# EsquematicoPotencia.net
KiCad netlist of a schematic drawn in EAGLE
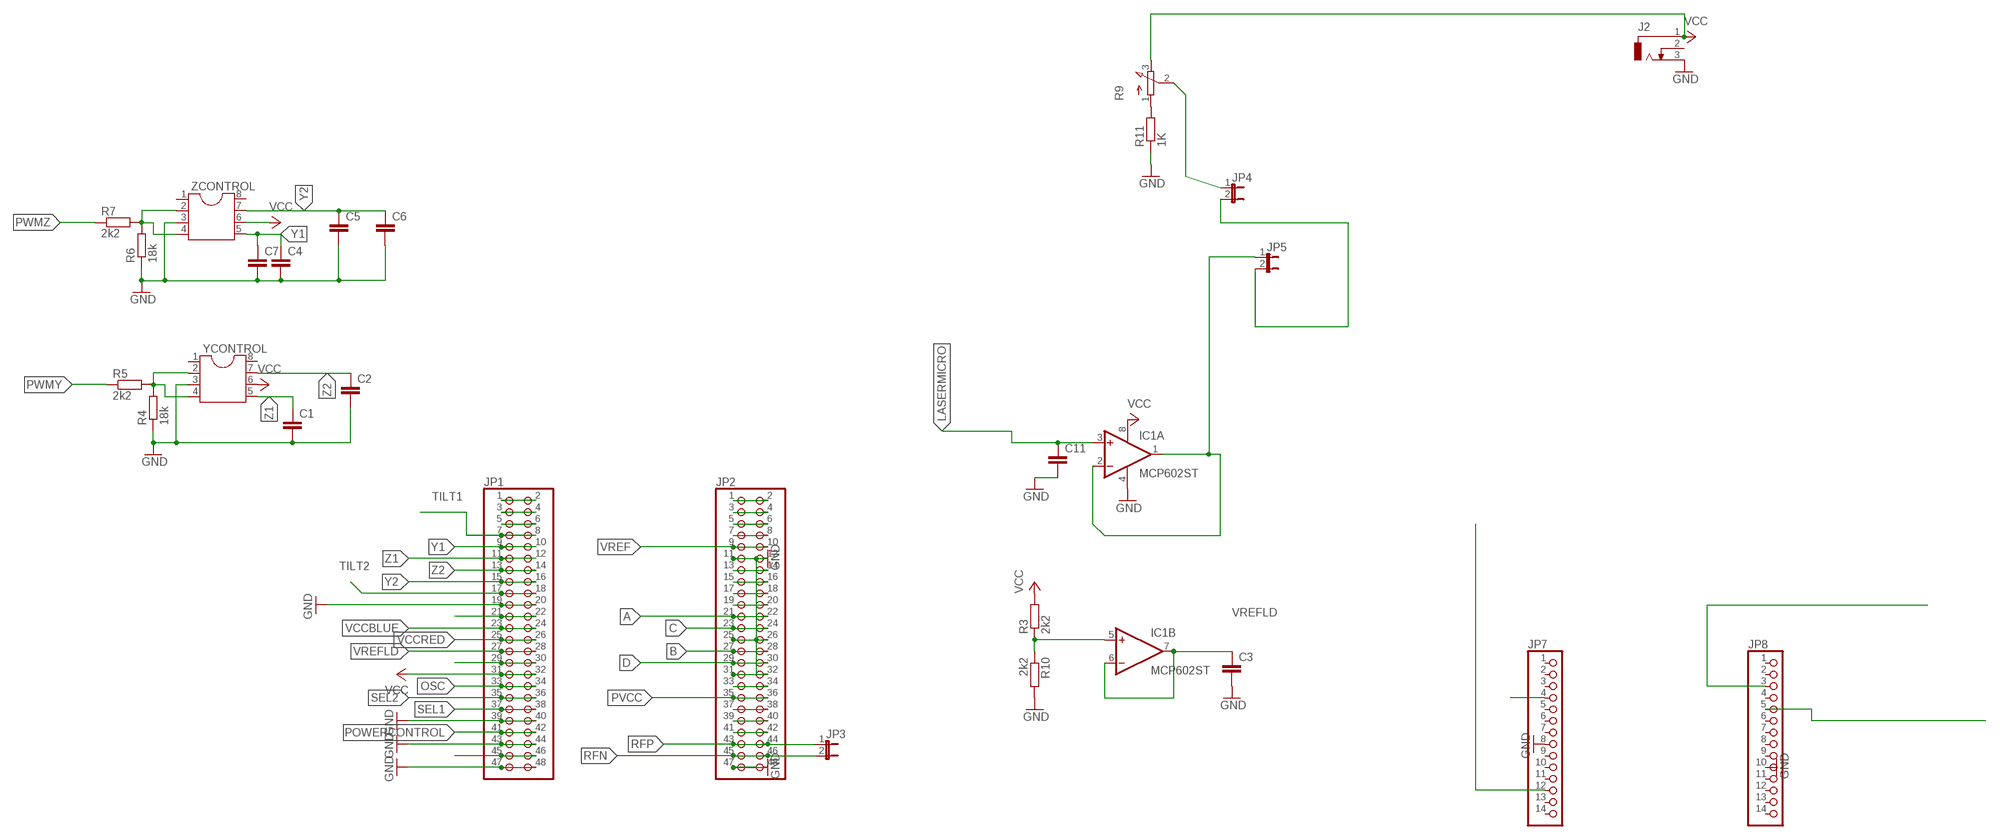
[diagram p0: schematic, sheet 1]

(export (version "E")
  (design (tool "Eeschema 10.0.6"))
  (components
    (comp (ref "C1")
      (value "C-EU025-024X044")
      (footprint "eagle-import:C025-024X044")
      (libsource (lib "eagle-import") (part "C-EU025-024X044"))
    )
    (comp (ref "C2")
      (value "C-EU025-024X044")
      (footprint "eagle-import:C025-024X044")
      (libsource (lib "eagle-import") (part "C-EU025-024X044"))
    )
    (comp (ref "C3")
      (value "C-EU025-024X044")
      (footprint "eagle-import:C025-024X044")
      (libsource (lib "eagle-import") (part "C-EU025-024X044"))
    )
    (comp (ref "C4")
      (value "C-EU025-024X044")
      (footprint "eagle-import:C025-024X044")
      (libsource (lib "eagle-import") (part "C-EU025-024X044"))
    )
    (comp (ref "C5")
      (value "C-EU025-024X044")
      (footprint "eagle-import:C025-024X044")
      (libsource (lib "eagle-import") (part "C-EU025-024X044"))
    )
    (comp (ref "C6")
      (value "C-EU025-024X044")
      (footprint "eagle-import:C025-024X044")
      (libsource (lib "eagle-import") (part "C-EU025-024X044"))
    )
    (comp (ref "C7")
      (value "C-EU025-024X044")
      (footprint "eagle-import:C025-024X044")
      (libsource (lib "eagle-import") (part "C-EU025-024X044"))
    )
    (comp (ref "C11")
      (value "C-EU025-024X044")
      (footprint "eagle-import:C025-024X044")
      (libsource (lib "eagle-import") (part "C-EU025-024X044"))
    )
    (comp (ref "IC1")
      (value "MCP602ST")
      (footprint "eagle-import:TSSOP8")
      (libsource (lib "eagle-import") (part "MCP602ST"))
    )
    (comp (ref "J2")
      (value "DCJ0303")
      (footprint "eagle-import:DCJ0303")
      (libsource (lib "eagle-import") (part "DCJ0303"))
    )
    (comp (ref "JP1")
      (value "PINHD-2X24")
      (footprint "eagle-import:2X24")
      (libsource (lib "eagle-import") (part "PINHD-2X24"))
    )
    (comp (ref "JP2")
      (value "PINHD-2X24")
      (footprint "eagle-import:2X24")
      (libsource (lib "eagle-import") (part "PINHD-2X24"))
    )
    (comp (ref "JP3")
      (value "JP1E")
      (footprint "eagle-import:JP1")
      (libsource (lib "eagle-import") (part "JP1E"))
    )
    (comp (ref "JP4")
      (value "JP1E")
      (footprint "eagle-import:JP1")
      (libsource (lib "eagle-import") (part "JP1E"))
    )
    (comp (ref "JP5")
      (value "JP1E")
      (footprint "eagle-import:JP1")
      (libsource (lib "eagle-import") (part "JP1E"))
    )
    (comp (ref "JP7")
      (value "PINHD-1X14")
      (footprint "eagle-import:1X14")
      (libsource (lib "eagle-import") (part "PINHD-1X14"))
    )
    (comp (ref "JP8")
      (value "PINHD-1X14")
      (footprint "eagle-import:1X14")
      (libsource (lib "eagle-import") (part "PINHD-1X14"))
    )
    (comp (ref "R3")
      (value "2k2")
      (footprint "eagle-import:0204_7")
      (libsource (lib "eagle-import") (part "R-EU_0204/7"))
    )
    (comp (ref "R4")
      (value "18k")
      (footprint "eagle-import:0204_7")
      (libsource (lib "eagle-import") (part "R-EU_0204/7"))
    )
    (comp (ref "R5")
      (value "2k2")
      (footprint "eagle-import:0204_7")
      (libsource (lib "eagle-import") (part "R-EU_0204/7"))
    )
    (comp (ref "R6")
      (value "18k")
      (footprint "eagle-import:0204_7")
      (libsource (lib "eagle-import") (part "R-EU_0204/7"))
    )
    (comp (ref "R7")
      (value "2k2")
      (footprint "eagle-import:0204_7")
      (libsource (lib "eagle-import") (part "R-EU_0204/7"))
    )
    (comp (ref "R9")
      (value "3RP/1610N")
      (footprint "eagle-import:3RP_1610N")
      (libsource (lib "eagle-import") (part "3RP/1610N"))
    )
    (comp (ref "R10")
      (value "2k2")
      (footprint "eagle-import:0204_7")
      (libsource (lib "eagle-import") (part "R-EU_0204/7"))
    )
    (comp (ref "R11")
      (value "1K")
      (footprint "eagle-import:0204_7")
      (libsource (lib "eagle-import") (part "R-EU_0204/7"))
    )
    (comp (ref "YCONTROL")
      (value "DIL8")
      (footprint "eagle-import:DIL08")
      (libsource (lib "eagle-import") (part "DIL8"))
    )
    (comp (ref "ZCONTROL")
      (value "DIL8")
      (footprint "eagle-import:DIL08")
      (libsource (lib "eagle-import") (part "DIL8"))
    )
  )
  (nets
    (net (code "1") (name "/TILT1") (class "Default")
      (node (ref "JP1") (pin "7") (pinfunction "7_7") (pintype "passive"))
      (node (ref "JP1") (pin "8") (pinfunction "8_8") (pintype "passive"))
    )
    (net (code "2") (name "/TILT2") (class "Default")
      (node (ref "JP1") (pin "17") (pinfunction "17_17") (pintype "passive"))
      (node (ref "JP1") (pin "18") (pinfunction "18_18") (pintype "passive"))
    )
    (net (code "3") (name "A") (class "Default")
      (node (ref "JP2") (pin "21") (pinfunction "21_21") (pintype "passive"))
      (node (ref "JP2") (pin "22") (pinfunction "22_22") (pintype "passive"))
    )
    (net (code "4") (name "B") (class "Default")
      (node (ref "JP2") (pin "27") (pinfunction "27_27") (pintype "passive"))
      (node (ref "JP2") (pin "28") (pinfunction "28_28") (pintype "passive"))
    )
    (net (code "5") (name "C") (class "Default")
      (node (ref "JP2") (pin "23") (pinfunction "23_23") (pintype "passive"))
      (node (ref "JP2") (pin "24") (pinfunction "24_24") (pintype "passive"))
    )
    (net (code "6") (name "D") (class "Default")
      (node (ref "JP2") (pin "29") (pinfunction "29_29") (pintype "passive"))
      (node (ref "JP2") (pin "30") (pinfunction "30_30") (pintype "passive"))
    )
    (net (code "7") (name "GND") (class "Default")
      (node (ref "C1") (pin "2") (pinfunction "2_2") (pintype "passive"))
      (node (ref "C11") (pin "2") (pinfunction "2_2") (pintype "passive"))
      (node (ref "C2") (pin "2") (pinfunction "2_2") (pintype "passive"))
      (node (ref "C3") (pin "2") (pinfunction "2_2") (pintype "passive"))
      (node (ref "C4") (pin "2") (pinfunction "2_2") (pintype "passive"))
      (node (ref "C5") (pin "2") (pinfunction "2_2") (pintype "passive"))
      (node (ref "C6") (pin "2") (pinfunction "2_2") (pintype "passive"))
      (node (ref "C7") (pin "2") (pinfunction "2_2") (pintype "passive"))
      (node (ref "IC1") (pin "4") (pinfunction "V-_4") (pintype "power_in"))
      (node (ref "J2") (pin "3") (pinfunction "3_3") (pintype "passive"))
      (node (ref "JP1") (pin "19") (pinfunction "19_19") (pintype "passive"))
      (node (ref "JP1") (pin "20") (pinfunction "20_20") (pintype "passive"))
      (node (ref "JP1") (pin "39") (pinfunction "39_39") (pintype "passive"))
      (node (ref "JP1") (pin "40") (pinfunction "40_40") (pintype "passive"))
      (node (ref "JP1") (pin "43") (pinfunction "43_43") (pintype "passive"))
      (node (ref "JP1") (pin "44") (pinfunction "44_44") (pintype "passive"))
      (node (ref "JP1") (pin "47") (pinfunction "47_47") (pintype "passive"))
      (node (ref "JP1") (pin "48") (pinfunction "48_48") (pintype "passive"))
      (node (ref "JP2") (pin "11") (pinfunction "11_11") (pintype "passive"))
      (node (ref "JP2") (pin "12") (pinfunction "12_12") (pintype "passive"))
      (node (ref "JP2") (pin "25") (pinfunction "25_25") (pintype "passive"))
      (node (ref "JP2") (pin "26") (pinfunction "26_26") (pintype "passive"))
      (node (ref "JP2") (pin "31") (pinfunction "31_31") (pintype "passive"))
      (node (ref "JP2") (pin "32") (pinfunction "32_32") (pintype "passive"))
      (node (ref "JP2") (pin "47") (pinfunction "47_47") (pintype "passive"))
      (node (ref "JP2") (pin "48") (pinfunction "48_48") (pintype "passive"))
      (node (ref "JP7") (pin "8") (pinfunction "8_8") (pintype "passive"))
      (node (ref "JP8") (pin "10") (pinfunction "10_10") (pintype "passive"))
      (node (ref "R10") (pin "2") (pinfunction "2_2") (pintype "passive"))
      (node (ref "R11") (pin "1") (pinfunction "1_1") (pintype "passive"))
      (node (ref "R4") (pin "1") (pinfunction "1_1") (pintype "passive"))
      (node (ref "R6") (pin "1") (pinfunction "1_1") (pintype "passive"))
      (node (ref "YCONTROL") (pin "3") (pinfunction "3_3") (pintype "passive"))
      (node (ref "ZCONTROL") (pin "3") (pinfunction "3_3") (pintype "passive"))
    )
    (net (code "8") (name "LASERMICRO") (class "Default")
      (node (ref "C11") (pin "1") (pinfunction "1_1") (pintype "passive"))
      (node (ref "IC1") (pin "3") (pinfunction "+IN_3") (pintype "input"))
      (node (ref "JP7") (pin "4") (pinfunction "4_4") (pintype "passive"))
    )
    (net (code "9") (name "Net-(IC1A--IN)") (class "Default")
      (node (ref "IC1") (pin "1") (pinfunction "OUT_1") (pintype "output"))
      (node (ref "IC1") (pin "2") (pinfunction "-IN_2") (pintype "input"))
      (node (ref "JP5") (pin "1") (pinfunction "1_1") (pintype "passive"))
    )
    (net (code "10") (name "Net-(IC1B-+IN)") (class "Default")
      (node (ref "IC1") (pin "5") (pinfunction "+IN_5") (pintype "input"))
      (node (ref "R10") (pin "1") (pinfunction "1_1") (pintype "passive"))
      (node (ref "R3") (pin "1") (pinfunction "1_1") (pintype "passive"))
    )
    (net (code "11") (name "Net-(JP1-Pad1)") (class "Default")
      (node (ref "JP1") (pin "1") (pinfunction "1_1") (pintype "passive"))
      (node (ref "JP1") (pin "2") (pinfunction "2_2") (pintype "passive"))
    )
    (net (code "12") (name "Net-(JP1-Pad3)") (class "Default")
      (node (ref "JP1") (pin "3") (pinfunction "3_3") (pintype "passive"))
      (node (ref "JP1") (pin "4") (pinfunction "4_4") (pintype "passive"))
    )
    (net (code "13") (name "Net-(JP1-Pad5)") (class "Default")
      (node (ref "JP1") (pin "5") (pinfunction "5_5") (pintype "passive"))
      (node (ref "JP1") (pin "6") (pinfunction "6_6") (pintype "passive"))
    )
    (net (code "14") (name "Net-(JP1-Pad21)") (class "Default")
      (node (ref "JP1") (pin "21") (pinfunction "21_21") (pintype "passive"))
      (node (ref "JP1") (pin "22") (pinfunction "22_22") (pintype "passive"))
    )
    (net (code "15") (name "Net-(JP1-Pad29)") (class "Default")
      (node (ref "JP1") (pin "29") (pinfunction "29_29") (pintype "passive"))
      (node (ref "JP1") (pin "30") (pinfunction "30_30") (pintype "passive"))
    )
    (net (code "16") (name "Net-(JP1-Pad45)") (class "Default")
      (node (ref "JP1") (pin "45") (pinfunction "45_45") (pintype "passive"))
      (node (ref "JP1") (pin "46") (pinfunction "46_46") (pintype "passive"))
    )
    (net (code "17") (name "Net-(JP2-Pad1)") (class "Default")
      (node (ref "JP2") (pin "1") (pinfunction "1_1") (pintype "passive"))
      (node (ref "JP2") (pin "2") (pinfunction "2_2") (pintype "passive"))
    )
    (net (code "18") (name "Net-(JP2-Pad3)") (class "Default")
      (node (ref "JP2") (pin "3") (pinfunction "3_3") (pintype "passive"))
      (node (ref "JP2") (pin "4") (pinfunction "4_4") (pintype "passive"))
    )
    (net (code "19") (name "Net-(JP2-Pad5)") (class "Default")
      (node (ref "JP2") (pin "5") (pinfunction "5_5") (pintype "passive"))
      (node (ref "JP2") (pin "6") (pinfunction "6_6") (pintype "passive"))
    )
    (net (code "20") (name "Net-(JP2-Pad7)") (class "Default")
      (node (ref "JP2") (pin "7") (pinfunction "7_7") (pintype "passive"))
      (node (ref "JP2") (pin "8") (pinfunction "8_8") (pintype "passive"))
    )
    (net (code "21") (name "Net-(JP2-Pad13)") (class "Default")
      (node (ref "JP2") (pin "13") (pinfunction "13_13") (pintype "passive"))
      (node (ref "JP2") (pin "14") (pinfunction "14_14") (pintype "passive"))
    )
    (net (code "22") (name "Net-(JP2-Pad15)") (class "Default")
      (node (ref "JP2") (pin "15") (pinfunction "15_15") (pintype "passive"))
      (node (ref "JP2") (pin "16") (pinfunction "16_16") (pintype "passive"))
    )
    (net (code "23") (name "Net-(JP2-Pad17)") (class "Default")
      (node (ref "JP2") (pin "17") (pinfunction "17_17") (pintype "passive"))
      (node (ref "JP2") (pin "18") (pinfunction "18_18") (pintype "passive"))
    )
    (net (code "24") (name "Net-(JP2-Pad19)") (class "Default")
      (node (ref "JP2") (pin "19") (pinfunction "19_19") (pintype "passive"))
      (node (ref "JP2") (pin "20") (pinfunction "20_20") (pintype "passive"))
    )
    (net (code "25") (name "Net-(JP2-Pad33)") (class "Default")
      (node (ref "JP2") (pin "33") (pinfunction "33_33") (pintype "passive"))
      (node (ref "JP2") (pin "34") (pinfunction "34_34") (pintype "passive"))
    )
    (net (code "26") (name "Net-(JP2-Pad37)") (class "Default")
      (node (ref "JP2") (pin "37") (pinfunction "37_37") (pintype "passive"))
      (node (ref "JP2") (pin "38") (pinfunction "38_38") (pintype "passive"))
    )
    (net (code "27") (name "Net-(JP2-Pad39)") (class "Default")
      (node (ref "JP2") (pin "39") (pinfunction "39_39") (pintype "passive"))
      (node (ref "JP2") (pin "40") (pinfunction "40_40") (pintype "passive"))
    )
    (net (code "28") (name "Net-(JP2-Pad41)") (class "Default")
      (node (ref "JP2") (pin "41") (pinfunction "41_41") (pintype "passive"))
      (node (ref "JP2") (pin "42") (pinfunction "42_42") (pintype "passive"))
    )
    (net (code "29") (name "Net-(R4-Pad2)") (class "Default")
      (node (ref "R4") (pin "2") (pinfunction "2_2") (pintype "passive"))
      (node (ref "R5") (pin "2") (pinfunction "2_2") (pintype "passive"))
      (node (ref "YCONTROL") (pin "2") (pinfunction "2_2") (pintype "passive"))
      (node (ref "YCONTROL") (pin "4") (pinfunction "4_4") (pintype "passive"))
    )
    (net (code "30") (name "Net-(R6-Pad2)") (class "Default")
      (node (ref "R6") (pin "2") (pinfunction "2_2") (pintype "passive"))
      (node (ref "R7") (pin "2") (pinfunction "2_2") (pintype "passive"))
      (node (ref "ZCONTROL") (pin "2") (pinfunction "2_2") (pintype "passive"))
      (node (ref "ZCONTROL") (pin "4") (pinfunction "4_4") (pintype "passive"))
    )
    (net (code "31") (name "Net-(R9-A)") (class "Default")
      (node (ref "R11") (pin "2") (pinfunction "2_2") (pintype "passive"))
      (node (ref "R9") (pin "1") (pinfunction "A_1") (pintype "passive"))
    )
    (net (code "32") (name "Net-(R9-S)") (class "Default")
      (node (ref "JP4") (pin "1") (pinfunction "1_1") (pintype "passive"))
      (node (ref "R9") (pin "2") (pinfunction "S_2") (pintype "passive"))
    )
    (net (code "33") (name "OSC") (class "Default")
      (node (ref "JP1") (pin "33") (pinfunction "33_33") (pintype "passive"))
      (node (ref "JP1") (pin "34") (pinfunction "34_34") (pintype "passive"))
    )
    (net (code "34") (name "POWERCONTROL") (class "Default")
      (node (ref "JP1") (pin "41") (pinfunction "41_41") (pintype "passive"))
      (node (ref "JP1") (pin "42") (pinfunction "42_42") (pintype "passive"))
      (node (ref "JP4") (pin "2") (pinfunction "2_2") (pintype "passive"))
      (node (ref "JP5") (pin "2") (pinfunction "2_2") (pintype "passive"))
    )
    (net (code "35") (name "PVCC") (class "Default")
      (node (ref "JP2") (pin "35") (pinfunction "35_35") (pintype "passive"))
      (node (ref "JP2") (pin "36") (pinfunction "36_36") (pintype "passive"))
    )
    (net (code "36") (name "PWMY") (class "Default")
      (node (ref "JP7") (pin "12") (pinfunction "12_12") (pintype "passive"))
      (node (ref "R5") (pin "1") (pinfunction "1_1") (pintype "passive"))
    )
    (net (code "37") (name "PWMZ") (class "Default")
      (node (ref "JP8") (pin "3") (pinfunction "3_3") (pintype "passive"))
      (node (ref "R7") (pin "1") (pinfunction "1_1") (pintype "passive"))
    )
    (net (code "38") (name "RFN") (class "Default")
      (node (ref "JP2") (pin "45") (pinfunction "45_45") (pintype "passive"))
      (node (ref "JP2") (pin "46") (pinfunction "46_46") (pintype "passive"))
      (node (ref "JP3") (pin "2") (pinfunction "2_2") (pintype "passive"))
    )
    (net (code "39") (name "RFP") (class "Default")
      (node (ref "JP2") (pin "43") (pinfunction "43_43") (pintype "passive"))
      (node (ref "JP2") (pin "44") (pinfunction "44_44") (pintype "passive"))
      (node (ref "JP3") (pin "1") (pinfunction "1_1") (pintype "passive"))
    )
    (net (code "40") (name "SEL1") (class "Default")
      (node (ref "JP1") (pin "37") (pinfunction "37_37") (pintype "passive"))
      (node (ref "JP1") (pin "38") (pinfunction "38_38") (pintype "passive"))
    )
    (net (code "41") (name "SEL2") (class "Default")
      (node (ref "JP1") (pin "35") (pinfunction "35_35") (pintype "passive"))
      (node (ref "JP1") (pin "36") (pinfunction "36_36") (pintype "passive"))
    )
    (net (code "42") (name "VCC") (class "Default")
      (node (ref "IC1") (pin "8") (pinfunction "V+_8") (pintype "power_in"))
      (node (ref "J2") (pin "1") (pinfunction "1_1") (pintype "passive"))
      (node (ref "JP1") (pin "31") (pinfunction "31_31") (pintype "passive"))
      (node (ref "JP1") (pin "32") (pinfunction "32_32") (pintype "passive"))
      (node (ref "R3") (pin "2") (pinfunction "2_2") (pintype "passive"))
      (node (ref "R9") (pin "3") (pinfunction "E_3") (pintype "passive"))
      (node (ref "YCONTROL") (pin "6") (pinfunction "6_6") (pintype "passive"))
      (node (ref "ZCONTROL") (pin "6") (pinfunction "6_6") (pintype "passive"))
    )
    (net (code "43") (name "VCCBLUE") (class "Default")
      (node (ref "JP1") (pin "23") (pinfunction "23_23") (pintype "passive"))
      (node (ref "JP1") (pin "24") (pinfunction "24_24") (pintype "passive"))
    )
    (net (code "44") (name "VCCRED") (class "Default")
      (node (ref "JP1") (pin "25") (pinfunction "25_25") (pintype "passive"))
      (node (ref "JP1") (pin "26") (pinfunction "26_26") (pintype "passive"))
    )
    (net (code "45") (name "VREF") (class "Default")
      (node (ref "JP2") (pin "10") (pinfunction "10_10") (pintype "passive"))
      (node (ref "JP2") (pin "9") (pinfunction "9_9") (pintype "passive"))
    )
    (net (code "46") (name "VREFLD") (class "Default")
      (node (ref "C3") (pin "1") (pinfunction "1_1") (pintype "passive"))
      (node (ref "IC1") (pin "6") (pinfunction "-IN_6") (pintype "input"))
      (node (ref "IC1") (pin "7") (pinfunction "OUT_7") (pintype "output"))
      (node (ref "JP1") (pin "27") (pinfunction "27_27") (pintype "passive"))
      (node (ref "JP1") (pin "28") (pinfunction "28_28") (pintype "passive"))
    )
    (net (code "47") (name "Y1") (class "Default")
      (node (ref "C4") (pin "1") (pinfunction "1_1") (pintype "passive"))
      (node (ref "C7") (pin "1") (pinfunction "1_1") (pintype "passive"))
      (node (ref "JP1") (pin "10") (pinfunction "10_10") (pintype "passive"))
      (node (ref "JP1") (pin "9") (pinfunction "9_9") (pintype "passive"))
      (node (ref "ZCONTROL") (pin "5") (pinfunction "5_5") (pintype "passive"))
    )
    (net (code "48") (name "Y2") (class "Default")
      (node (ref "C5") (pin "1") (pinfunction "1_1") (pintype "passive"))
      (node (ref "C6") (pin "1") (pinfunction "1_1") (pintype "passive"))
      (node (ref "JP1") (pin "15") (pinfunction "15_15") (pintype "passive"))
      (node (ref "JP1") (pin "16") (pinfunction "16_16") (pintype "passive"))
      (node (ref "ZCONTROL") (pin "7") (pinfunction "7_7") (pintype "passive"))
    )
    (net (code "49") (name "Z1") (class "Default")
      (node (ref "C1") (pin "1") (pinfunction "1_1") (pintype "passive"))
      (node (ref "JP1") (pin "11") (pinfunction "11_11") (pintype "passive"))
      (node (ref "JP1") (pin "12") (pinfunction "12_12") (pintype "passive"))
      (node (ref "YCONTROL") (pin "5") (pinfunction "5_5") (pintype "passive"))
    )
    (net (code "50") (name "Z2") (class "Default")
      (node (ref "C2") (pin "1") (pinfunction "1_1") (pintype "passive"))
      (node (ref "JP1") (pin "13") (pinfunction "13_13") (pintype "passive"))
      (node (ref "JP1") (pin "14") (pinfunction "14_14") (pintype "passive"))
      (node (ref "YCONTROL") (pin "7") (pinfunction "7_7") (pintype "passive"))
    )
    (net (code "51") (name "unconnected-(J2-Pad2)") (class "Default")
      (node (ref "J2") (pin "2") (pinfunction "2_2") (pintype "passive"))
    )
    (net (code "52") (name "unconnected-(JP7-Pad1)") (class "Default")
      (node (ref "JP7") (pin "1") (pinfunction "1_1") (pintype "passive"))
    )
    (net (code "53") (name "unconnected-(JP7-Pad2)") (class "Default")
      (node (ref "JP7") (pin "2") (pinfunction "2_2") (pintype "passive"))
    )
    (net (code "54") (name "unconnected-(JP7-Pad3)") (class "Default")
      (node (ref "JP7") (pin "3") (pinfunction "3_3") (pintype "passive"))
    )
    (net (code "55") (name "unconnected-(JP7-Pad5)") (class "Default")
      (node (ref "JP7") (pin "5") (pinfunction "5_5") (pintype "passive"))
    )
    (net (code "56") (name "unconnected-(JP7-Pad6)") (class "Default")
      (node (ref "JP7") (pin "6") (pinfunction "6_6") (pintype "passive"))
    )
    (net (code "57") (name "unconnected-(JP7-Pad7)") (class "Default")
      (node (ref "JP7") (pin "7") (pinfunction "7_7") (pintype "passive"))
    )
    (net (code "58") (name "unconnected-(JP7-Pad9)") (class "Default")
      (node (ref "JP7") (pin "9") (pinfunction "9_9") (pintype "passive"))
    )
    (net (code "59") (name "unconnected-(JP7-Pad10)") (class "Default")
      (node (ref "JP7") (pin "10") (pinfunction "10_10") (pintype "passive"))
    )
    (net (code "60") (name "unconnected-(JP7-Pad11)") (class "Default")
      (node (ref "JP7") (pin "11") (pinfunction "11_11") (pintype "passive"))
    )
    (net (code "61") (name "unconnected-(JP7-Pad13)") (class "Default")
      (node (ref "JP7") (pin "13") (pinfunction "13_13") (pintype "passive"))
    )
    (net (code "62") (name "unconnected-(JP7-Pad14)") (class "Default")
      (node (ref "JP7") (pin "14") (pinfunction "14_14") (pintype "passive"))
    )
    (net (code "63") (name "unconnected-(JP8-Pad1)") (class "Default")
      (node (ref "JP8") (pin "1") (pinfunction "1_1") (pintype "passive"))
    )
    (net (code "64") (name "unconnected-(JP8-Pad2)") (class "Default")
      (node (ref "JP8") (pin "2") (pinfunction "2_2") (pintype "passive"))
    )
    (net (code "65") (name "unconnected-(JP8-Pad4)") (class "Default")
      (node (ref "JP8") (pin "4") (pinfunction "4_4") (pintype "passive"))
    )
    (net (code "66") (name "unconnected-(JP8-Pad5)") (class "Default")
      (node (ref "JP8") (pin "5") (pinfunction "5_5") (pintype "passive"))
    )
    (net (code "67") (name "unconnected-(JP8-Pad6)") (class "Default")
      (node (ref "JP8") (pin "6") (pinfunction "6_6") (pintype "passive"))
    )
    (net (code "68") (name "unconnected-(JP8-Pad7)") (class "Default")
      (node (ref "JP8") (pin "7") (pinfunction "7_7") (pintype "passive"))
    )
    (net (code "69") (name "unconnected-(JP8-Pad8)") (class "Default")
      (node (ref "JP8") (pin "8") (pinfunction "8_8") (pintype "passive"))
    )
    (net (code "70") (name "unconnected-(JP8-Pad9)") (class "Default")
      (node (ref "JP8") (pin "9") (pinfunction "9_9") (pintype "passive"))
    )
    (net (code "71") (name "unconnected-(JP8-Pad11)") (class "Default")
      (node (ref "JP8") (pin "11") (pinfunction "11_11") (pintype "passive"))
    )
    (net (code "72") (name "unconnected-(JP8-Pad12)") (class "Default")
      (node (ref "JP8") (pin "12") (pinfunction "12_12") (pintype "passive"))
    )
    (net (code "73") (name "unconnected-(JP8-Pad13)") (class "Default")
      (node (ref "JP8") (pin "13") (pinfunction "13_13") (pintype "passive"))
    )
    (net (code "74") (name "unconnected-(JP8-Pad14)") (class "Default")
      (node (ref "JP8") (pin "14") (pinfunction "14_14") (pintype "passive"))
    )
    (net (code "75") (name "unconnected-(YCONTROL-Pad1)") (class "Default")
      (node (ref "YCONTROL") (pin "1") (pinfunction "1_1") (pintype "passive"))
    )
    (net (code "76") (name "unconnected-(YCONTROL-Pad8)") (class "Default")
      (node (ref "YCONTROL") (pin "8") (pinfunction "8_8") (pintype "passive"))
    )
    (net (code "77") (name "unconnected-(ZCONTROL-Pad1)") (class "Default")
      (node (ref "ZCONTROL") (pin "1") (pinfunction "1_1") (pintype "passive"))
    )
    (net (code "78") (name "unconnected-(ZCONTROL-Pad8)") (class "Default")
      (node (ref "ZCONTROL") (pin "8") (pinfunction "8_8") (pintype "passive"))
    )
  )
)
